# UI_MAIN.net
KiCad netlist of a schematic drawn in Altium Designer
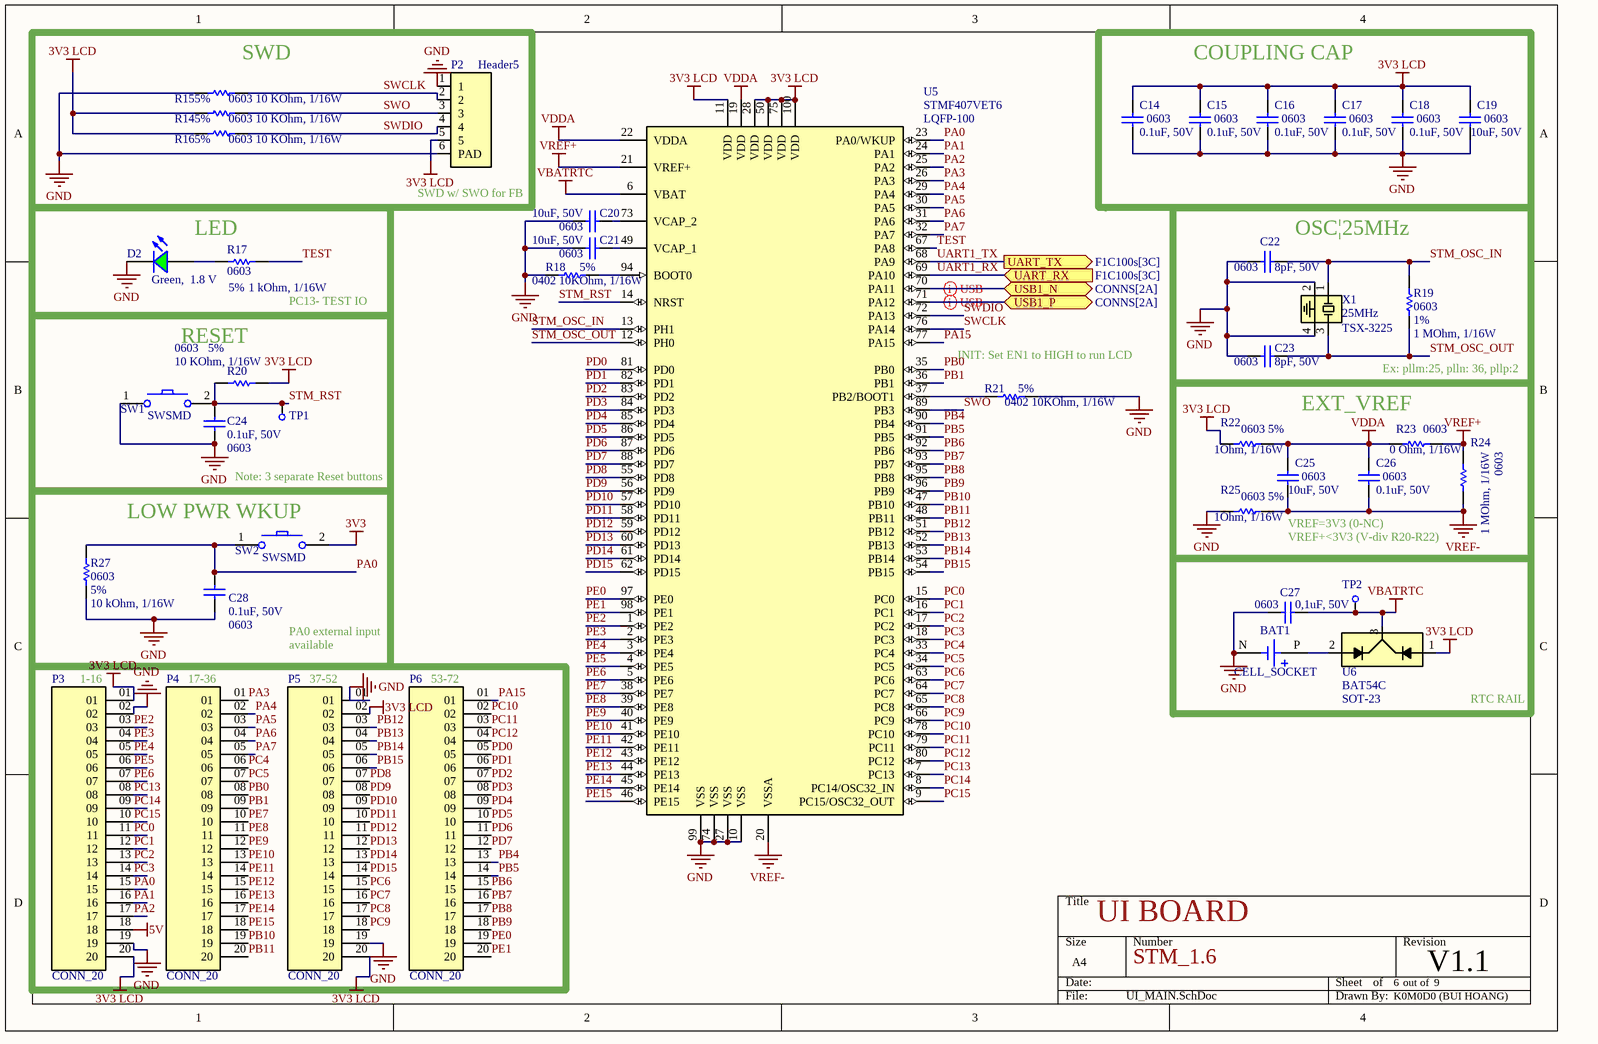
[diagram p0: UI_MAIN.SchDoc]

(export (version "E")
  (design (tool "Eeschema 10.0.6"))
  (components
    (comp (ref "BAT1")
      (value "CELL_SOCKET")
      (footprint "CELL_SOCKET")
      (description "Battery Holder (CELL_PIN)")
      (libsource (lib "DisplayLib") (part "CELL_SOCKET"))
    )
    (comp (ref "C14")
      (value "0.1uF, 50V")
      (footprint "C_0603")
      (description "CAP_0603")
      (fields (field (name "PACKAGE") "0603"))
      (libsource (lib "DisplayLib") (part "CAP_0603"))
    )
    (comp (ref "C15")
      (value "0.1uF, 50V")
      (footprint "C_0603")
      (description "CAP_0603")
      (fields (field (name "PACKAGE") "0603"))
      (libsource (lib "DisplayLib") (part "CAP_0603"))
    )
    (comp (ref "C16")
      (value "0.1uF, 50V")
      (footprint "C_0603")
      (description "CAP_0603")
      (fields (field (name "PACKAGE") "0603"))
      (libsource (lib "DisplayLib") (part "CAP_0603"))
    )
    (comp (ref "C17")
      (value "0.1uF, 50V")
      (footprint "C_0603")
      (description "CAP_0603")
      (fields (field (name "PACKAGE") "0603"))
      (libsource (lib "DisplayLib") (part "CAP_0603"))
    )
    (comp (ref "C18")
      (value "0.1uF, 50V")
      (footprint "C_0603")
      (description "CAP_0603")
      (fields (field (name "PACKAGE") "0603"))
      (libsource (lib "DisplayLib") (part "CAP_0603"))
    )
    (comp (ref "C19")
      (value "10uF, 50V")
      (footprint "C_0603")
      (description "CAP_0603")
      (fields (field (name "PACKAGE") "0603"))
      (libsource (lib "DisplayLib") (part "CAP_0603"))
    )
    (comp (ref "C20")
      (value "10uF, 50V")
      (footprint "C_0603")
      (description "CAP_0603")
      (fields (field (name "PACKAGE") "0603"))
      (libsource (lib "DisplayLib") (part "CAP_0603"))
    )
    (comp (ref "C21")
      (value "10uF, 50V")
      (footprint "C_0603")
      (description "CAP_0603")
      (fields (field (name "PACKAGE") "0603"))
      (libsource (lib "DisplayLib") (part "CAP_0603"))
    )
    (comp (ref "C22")
      (value "8pF, 50V")
      (footprint "C_0603")
      (description "CAP_0603")
      (fields (field (name "PACKAGE") "0603"))
      (libsource (lib "DisplayLib") (part "CAP_0603"))
    )
    (comp (ref "C23")
      (value "8pF, 50V")
      (footprint "C_0603")
      (description "CAP_0603")
      (fields (field (name "PACKAGE") "0603"))
      (libsource (lib "DisplayLib") (part "CAP_0603"))
    )
    (comp (ref "C24")
      (value "0.1uF, 50V")
      (footprint "C_0603")
      (description "CAP_0603")
      (fields (field (name "PACKAGE") "0603"))
      (libsource (lib "DisplayLib") (part "CAP_0603"))
    )
    (comp (ref "C25")
      (value "10uF, 50V")
      (footprint "C_0603")
      (description "CAP_0603")
      (fields (field (name "PACKAGE") "0603"))
      (libsource (lib "DisplayLib") (part "CAP_0603"))
    )
    (comp (ref "C26")
      (value "0.1uF, 50V")
      (footprint "C_0603")
      (description "CAP_0603")
      (fields (field (name "PACKAGE") "0603"))
      (libsource (lib "DisplayLib") (part "CAP_0603"))
    )
    (comp (ref "C27")
      (value "0,1uF, 50V")
      (footprint "C_0603")
      (description "CAP_0603")
      (fields (field (name "PACKAGE") "0603"))
      (libsource (lib "DisplayLib") (part "CAP_0603"))
    )
    (comp (ref "C28")
      (value "0.1uF, 50V")
      (footprint "C_0603")
      (description "CAP_0603")
      (fields (field (name "PACKAGE") "0603"))
      (libsource (lib "DisplayLib") (part "CAP_0603"))
    )
    (comp (ref "D2")
      (value "Green,  1.8 V")
      (footprint "LED_0603")
      (description "Green LED")
      (libsource (lib "DisplayLib") (part "GREEN"))
    )
    (comp (ref "P2")
      (value "Header5")
      (footprint "CONN_Header5")
      (description "Header 5 pins (2.54mm)")
      (libsource (lib "DisplayLib") (part "HEADER5"))
    )
    (comp (ref "P3")
      (value "CONN_20")
      (footprint "CONN_20")
      (description "Header 20 pins (2.54mm)")
      (libsource (lib "DisplayLib") (part "CONN_20"))
    )
    (comp (ref "P4")
      (value "CONN_20")
      (footprint "CONN_20")
      (description "Header 20 pins (2.54mm)")
      (libsource (lib "DisplayLib") (part "CONN_20"))
    )
    (comp (ref "P5")
      (value "CONN_20")
      (footprint "CONN_20")
      (description "Header 20 pins (2.54mm)")
      (libsource (lib "DisplayLib") (part "CONN_20"))
    )
    (comp (ref "P6")
      (value "CONN_20")
      (footprint "CONN_20")
      (description "Header 20 pins (2.54mm)")
      (libsource (lib "DisplayLib") (part "CONN_20"))
    )
    (comp (ref "R14")
      (value "10 KOhm, 1/16W")
      (footprint "R_0603")
      (description "RES_0603")
      (fields (field (name "PACKAGE") "0603") (field (name "ACC") "5%"))
      (libsource (lib "DisplayLib") (part "RES_0603"))
    )
    (comp (ref "R15")
      (value "10 KOhm, 1/16W")
      (footprint "R_0603")
      (description "RES_0603")
      (fields (field (name "PACKAGE") "0603") (field (name "ACC") "5%"))
      (libsource (lib "DisplayLib") (part "RES_0603"))
    )
    (comp (ref "R16")
      (value "10 KOhm, 1/16W")
      (footprint "R_0603")
      (description "RES_0603")
      (fields (field (name "PACKAGE") "0603") (field (name "ACC") "5%"))
      (libsource (lib "DisplayLib") (part "RES_0603"))
    )
    (comp (ref "R17")
      (value "1 kOhm, 1/16W")
      (footprint "R_0603")
      (description "RES_0603")
      (fields (field (name "PACKAGE") "0603") (field (name "ACC") "5%"))
      (libsource (lib "DisplayLib") (part "RES_0603"))
    )
    (comp (ref "R18")
      (value "10KOhm, 1/16W")
      (footprint "R_0402")
      (description "RES_0402")
      (fields (field (name "PACKAGE") "0402") (field (name "ACC") "5%"))
      (libsource (lib "DisplayLib") (part "RES_0402"))
    )
    (comp (ref "R19")
      (value "1 MOhm, 1/16W")
      (footprint "R_0603")
      (description "RES_0603")
      (fields (field (name "PACKAGE") "0603") (field (name "ACC") "1%"))
      (libsource (lib "DisplayLib") (part "RES_0603"))
    )
    (comp (ref "R20")
      (value "10 KOhm, 1/16W")
      (footprint "R_0603")
      (description "RES_0603")
      (fields (field (name "PACKAGE") "0603") (field (name "ACC") "5%"))
      (libsource (lib "DisplayLib") (part "RES_0603"))
    )
    (comp (ref "R21")
      (value "10KOhm, 1/16W")
      (footprint "R_0402")
      (description "RES_0402")
      (fields (field (name "PACKAGE") "0402") (field (name "ACC") "5%"))
      (libsource (lib "DisplayLib") (part "RES_0402"))
    )
    (comp (ref "R22")
      (value "1Ohm, 1/16W")
      (footprint "R_0603")
      (description "RES_0603")
      (fields (field (name "PACKAGE") "0603") (field (name "ACC") "5%"))
      (libsource (lib "DisplayLib") (part "RES_0603"))
    )
    (comp (ref "R23")
      (value "0 Ohm, 1/16W")
      (footprint "R_0603")
      (description "RES_0603")
      (fields (field (name "PACKAGE") "0603"))
      (libsource (lib "DisplayLib") (part "RES_0603"))
    )
    (comp (ref "R24")
      (value "1 MOhm, 1/16W")
      (footprint "R_0603")
      (description "RES_0603")
      (fields (field (name "PACKAGE") "0603"))
      (libsource (lib "DisplayLib") (part "RES_0603"))
    )
    (comp (ref "R25")
      (value "1Ohm, 1/16W")
      (footprint "R_0603")
      (description "RES_0603")
      (fields (field (name "PACKAGE") "0603") (field (name "ACC") "5%"))
      (libsource (lib "DisplayLib") (part "RES_0603"))
    )
    (comp (ref "R27")
      (value "10 kOhm, 1/16W")
      (footprint "R_0603")
      (description "RES_0603")
      (fields (field (name "PACKAGE") "0603") (field (name "ACC") "5%"))
      (libsource (lib "DisplayLib") (part "RES_0603"))
    )
    (comp (ref "SW1")
      (value "SWSMD")
      (footprint "SW_SMD_NOGND")
      (description "SW_SMD")
      (libsource (lib "DisplayLib") (part "SWSMD_NOGND"))
    )
    (comp (ref "SW2")
      (value "SWSMD")
      (footprint "SW_SMD_NOGND")
      (description "SW_SMD")
      (libsource (lib "DisplayLib") (part "SWSMD_NOGND"))
    )
    (comp (ref "TP1")
      (value "TESTPT")
      (footprint "TESTPT")
      (description "Test point")
      (libsource (lib "DisplayLib") (part "TESTPT"))
    )
    (comp (ref "TP2")
      (value "TESTPT")
      (footprint "TESTPT")
      (description "Test point")
      (libsource (lib "DisplayLib") (part "TESTPT"))
    )
    (comp (ref "U5")
      (value "STMF407VET6")
      (footprint "PKG_LQFP-100")
      (fields (field (name "PACKAGE") "LQFP-100"))
      (libsource (lib "DisplayLib") (part "STMF407VET6"))
    )
    (comp (ref "U6")
      (value "BAT54C")
      (footprint "PKG_SOT-23")
      (description "P-Channel 30 V 4A (Ta) 1.4W (Ta) Surface Mount SOT-23-3")
      (fields (field (name "PACKAGE") "SOT-23"))
      (libsource (lib "DisplayLib") (part "BAT54C"))
    )
    (comp (ref "X1")
      (value "25MHz")
      (footprint "PKG_TSX-3225")
      (description "Crystal, 25 MHz, -30 to 85 degC, 3.2 x 2.5 x 0.9 mm SMD")
      (fields (field (name "PACKAGE") "TSX-3225"))
      (libsource (lib "DisplayLib") (part "XTAL"))
    )
  )
  (nets
    (net (code "1") (name "/PA0") (class "Default")
      (node (ref "C28") (pin "2") (pinfunction "2_2") (pintype "passive"))
      (node (ref "P3") (pin "15") (pinfunction "15_15") (pintype "passive"))
      (node (ref "R27") (pin "2") (pinfunction "2_2") (pintype "passive"))
      (node (ref "SW2") (pin "1") (pinfunction "1_1") (pintype "passive"))
      (node (ref "U5") (pin "23") (pinfunction "PA0/WKUP_23") (pintype "bidirectional"))
    )
    (net (code "2") (name "/PA1") (class "Default")
      (node (ref "P3") (pin "16") (pinfunction "16_16") (pintype "passive"))
      (node (ref "U5") (pin "24") (pinfunction "PA1_24") (pintype "bidirectional"))
    )
    (net (code "3") (name "/PA2") (class "Default")
      (node (ref "P3") (pin "17") (pinfunction "17_17") (pintype "passive"))
      (node (ref "U5") (pin "25") (pinfunction "PA2_25") (pintype "bidirectional"))
    )
    (net (code "4") (name "/PA3") (class "Default")
      (node (ref "P4") (pin "01") (pinfunction "01_01") (pintype "passive"))
      (node (ref "U5") (pin "26") (pinfunction "PA3_26") (pintype "bidirectional"))
    )
    (net (code "5") (name "/PA4") (class "Default")
      (node (ref "P4") (pin "02") (pinfunction "02_02") (pintype "passive"))
      (node (ref "U5") (pin "29") (pinfunction "PA4_29") (pintype "bidirectional"))
    )
    (net (code "6") (name "/PA5") (class "Default")
      (node (ref "P4") (pin "03") (pinfunction "03_03") (pintype "passive"))
      (node (ref "U5") (pin "30") (pinfunction "PA5_30") (pintype "bidirectional"))
    )
    (net (code "7") (name "/PA6") (class "Default")
      (node (ref "P4") (pin "04") (pinfunction "04_04") (pintype "passive"))
      (node (ref "U5") (pin "31") (pinfunction "PA6_31") (pintype "bidirectional"))
    )
    (net (code "8") (name "/PA7") (class "Default")
      (node (ref "P4") (pin "05") (pinfunction "05_05") (pintype "passive"))
      (node (ref "U5") (pin "32") (pinfunction "PA7_32") (pintype "bidirectional"))
    )
    (net (code "9") (name "/PA15") (class "Default")
      (node (ref "P6") (pin "01") (pinfunction "01_01") (pintype "passive"))
      (node (ref "U5") (pin "77") (pinfunction "PA15_77") (pintype "bidirectional"))
    )
    (net (code "10") (name "/PB0") (class "Default")
      (node (ref "P4") (pin "08") (pinfunction "08_08") (pintype "passive"))
      (node (ref "U5") (pin "35") (pinfunction "PB0_35") (pintype "bidirectional"))
    )
    (net (code "11") (name "/PB1") (class "Default")
      (node (ref "P4") (pin "09") (pinfunction "09_09") (pintype "passive"))
      (node (ref "U5") (pin "36") (pinfunction "PB1_36") (pintype "bidirectional"))
    )
    (net (code "12") (name "/PB4") (class "Default")
      (node (ref "P6") (pin "13") (pinfunction "13_13") (pintype "passive"))
      (node (ref "U5") (pin "90") (pinfunction "PB4_90") (pintype "bidirectional"))
    )
    (net (code "13") (name "/PB5") (class "Default")
      (node (ref "P6") (pin "14") (pinfunction "14_14") (pintype "passive"))
      (node (ref "U5") (pin "91") (pinfunction "PB5_91") (pintype "bidirectional"))
    )
    (net (code "14") (name "/PB6") (class "Default")
      (node (ref "P6") (pin "15") (pinfunction "15_15") (pintype "passive"))
      (node (ref "U5") (pin "92") (pinfunction "PB6_92") (pintype "bidirectional"))
    )
    (net (code "15") (name "/PB7") (class "Default")
      (node (ref "P6") (pin "16") (pinfunction "16_16") (pintype "passive"))
      (node (ref "U5") (pin "93") (pinfunction "PB7_93") (pintype "bidirectional"))
    )
    (net (code "16") (name "/PB8") (class "Default")
      (node (ref "P6") (pin "17") (pinfunction "17_17") (pintype "passive"))
      (node (ref "U5") (pin "95") (pinfunction "PB8_95") (pintype "bidirectional"))
    )
    (net (code "17") (name "/PB9") (class "Default")
      (node (ref "P6") (pin "18") (pinfunction "18_18") (pintype "passive"))
      (node (ref "U5") (pin "96") (pinfunction "PB9_96") (pintype "bidirectional"))
    )
    (net (code "18") (name "/PB10") (class "Default")
      (node (ref "P4") (pin "19") (pinfunction "19_19") (pintype "passive"))
      (node (ref "U5") (pin "47") (pinfunction "PB10_47") (pintype "bidirectional"))
    )
    (net (code "19") (name "/PB11") (class "Default")
      (node (ref "P4") (pin "20") (pinfunction "20_20") (pintype "passive"))
      (node (ref "U5") (pin "48") (pinfunction "PB11_48") (pintype "bidirectional"))
    )
    (net (code "20") (name "/PB12") (class "Default")
      (node (ref "P5") (pin "03") (pinfunction "03_03") (pintype "passive"))
      (node (ref "U5") (pin "51") (pinfunction "PB12_51") (pintype "bidirectional"))
    )
    (net (code "21") (name "/PB13") (class "Default")
      (node (ref "P5") (pin "04") (pinfunction "04_04") (pintype "passive"))
      (node (ref "U5") (pin "52") (pinfunction "PB13_52") (pintype "bidirectional"))
    )
    (net (code "22") (name "/PB14") (class "Default")
      (node (ref "P5") (pin "05") (pinfunction "05_05") (pintype "passive"))
      (node (ref "U5") (pin "53") (pinfunction "PB14_53") (pintype "bidirectional"))
    )
    (net (code "23") (name "/PB15") (class "Default")
      (node (ref "P5") (pin "06") (pinfunction "06_06") (pintype "passive"))
      (node (ref "U5") (pin "54") (pinfunction "PB15_54") (pintype "bidirectional"))
    )
    (net (code "24") (name "/PC0") (class "Default")
      (node (ref "P3") (pin "11") (pinfunction "11_11") (pintype "passive"))
      (node (ref "U5") (pin "15") (pinfunction "PC0_15") (pintype "bidirectional"))
    )
    (net (code "25") (name "/PC1") (class "Default")
      (node (ref "P3") (pin "12") (pinfunction "12_12") (pintype "passive"))
      (node (ref "U5") (pin "16") (pinfunction "PC1_16") (pintype "bidirectional"))
    )
    (net (code "26") (name "/PC2") (class "Default")
      (node (ref "P3") (pin "13") (pinfunction "13_13") (pintype "passive"))
      (node (ref "U5") (pin "17") (pinfunction "PC2_17") (pintype "bidirectional"))
    )
    (net (code "27") (name "/PC3") (class "Default")
      (node (ref "P3") (pin "14") (pinfunction "14_14") (pintype "passive"))
      (node (ref "U5") (pin "18") (pinfunction "PC3_18") (pintype "bidirectional"))
    )
    (net (code "28") (name "/PC4") (class "Default")
      (node (ref "P4") (pin "06") (pinfunction "06_06") (pintype "passive"))
      (node (ref "U5") (pin "33") (pinfunction "PC4_33") (pintype "bidirectional"))
    )
    (net (code "29") (name "/PC5") (class "Default")
      (node (ref "P4") (pin "07") (pinfunction "07_07") (pintype "passive"))
      (node (ref "U5") (pin "34") (pinfunction "PC5_34") (pintype "bidirectional"))
    )
    (net (code "30") (name "/PC6") (class "Default")
      (node (ref "P5") (pin "15") (pinfunction "15_15") (pintype "passive"))
      (node (ref "U5") (pin "63") (pinfunction "PC6_63") (pintype "bidirectional"))
    )
    (net (code "31") (name "/PC7") (class "Default")
      (node (ref "P5") (pin "16") (pinfunction "16_16") (pintype "passive"))
      (node (ref "U5") (pin "64") (pinfunction "PC7_64") (pintype "bidirectional"))
    )
    (net (code "32") (name "/PC8") (class "Default")
      (node (ref "P5") (pin "17") (pinfunction "17_17") (pintype "passive"))
      (node (ref "U5") (pin "65") (pinfunction "PC8_65") (pintype "bidirectional"))
    )
    (net (code "33") (name "/PC9") (class "Default")
      (node (ref "P5") (pin "18") (pinfunction "18_18") (pintype "passive"))
      (node (ref "U5") (pin "66") (pinfunction "PC9_66") (pintype "bidirectional"))
    )
    (net (code "34") (name "/PC10") (class "Default")
      (node (ref "P6") (pin "02") (pinfunction "02_02") (pintype "passive"))
      (node (ref "U5") (pin "78") (pinfunction "PC10_78") (pintype "bidirectional"))
    )
    (net (code "35") (name "/PC11") (class "Default")
      (node (ref "P6") (pin "03") (pinfunction "03_03") (pintype "passive"))
      (node (ref "U5") (pin "79") (pinfunction "PC11_79") (pintype "bidirectional"))
    )
    (net (code "36") (name "/PC12") (class "Default")
      (node (ref "P6") (pin "04") (pinfunction "04_04") (pintype "passive"))
      (node (ref "U5") (pin "80") (pinfunction "PC12_80") (pintype "bidirectional"))
    )
    (net (code "37") (name "/PC13") (class "Default")
      (node (ref "P3") (pin "08") (pinfunction "08_08") (pintype "passive"))
      (node (ref "U5") (pin "7") (pinfunction "PC13_7") (pintype "bidirectional"))
    )
    (net (code "38") (name "/PC14") (class "Default")
      (node (ref "P3") (pin "09") (pinfunction "09_09") (pintype "passive"))
      (node (ref "U5") (pin "8") (pinfunction "PC14/OSC32_IN_8") (pintype "bidirectional"))
    )
    (net (code "39") (name "/PC15") (class "Default")
      (node (ref "P3") (pin "10") (pinfunction "10_10") (pintype "passive"))
      (node (ref "U5") (pin "9") (pinfunction "PC15/OSC32_OUT_9") (pintype "bidirectional"))
    )
    (net (code "40") (name "/PD0") (class "Default")
      (node (ref "P6") (pin "05") (pinfunction "05_05") (pintype "passive"))
      (node (ref "U5") (pin "81") (pinfunction "PD0_81") (pintype "bidirectional"))
    )
    (net (code "41") (name "/PD1") (class "Default")
      (node (ref "P6") (pin "06") (pinfunction "06_06") (pintype "passive"))
      (node (ref "U5") (pin "82") (pinfunction "PD1_82") (pintype "bidirectional"))
    )
    (net (code "42") (name "/PD2") (class "Default")
      (node (ref "P6") (pin "07") (pinfunction "07_07") (pintype "passive"))
      (node (ref "U5") (pin "83") (pinfunction "PD2_83") (pintype "bidirectional"))
    )
    (net (code "43") (name "/PD3") (class "Default")
      (node (ref "P6") (pin "08") (pinfunction "08_08") (pintype "passive"))
      (node (ref "U5") (pin "84") (pinfunction "PD3_84") (pintype "bidirectional"))
    )
    (net (code "44") (name "/PD4") (class "Default")
      (node (ref "P6") (pin "09") (pinfunction "09_09") (pintype "passive"))
      (node (ref "U5") (pin "85") (pinfunction "PD4_85") (pintype "bidirectional"))
    )
    (net (code "45") (name "/PD5") (class "Default")
      (node (ref "P6") (pin "10") (pinfunction "10_10") (pintype "passive"))
      (node (ref "U5") (pin "86") (pinfunction "PD5_86") (pintype "bidirectional"))
    )
    (net (code "46") (name "/PD6") (class "Default")
      (node (ref "P6") (pin "11") (pinfunction "11_11") (pintype "passive"))
      (node (ref "U5") (pin "87") (pinfunction "PD6_87") (pintype "bidirectional"))
    )
    (net (code "47") (name "/PD7") (class "Default")
      (node (ref "P6") (pin "12") (pinfunction "12_12") (pintype "passive"))
      (node (ref "U5") (pin "88") (pinfunction "PD7_88") (pintype "bidirectional"))
    )
    (net (code "48") (name "/PD8") (class "Default")
      (node (ref "P5") (pin "07") (pinfunction "07_07") (pintype "passive"))
      (node (ref "U5") (pin "55") (pinfunction "PD8_55") (pintype "bidirectional"))
    )
    (net (code "49") (name "/PD9") (class "Default")
      (node (ref "P5") (pin "08") (pinfunction "08_08") (pintype "passive"))
      (node (ref "U5") (pin "56") (pinfunction "PD9_56") (pintype "bidirectional"))
    )
    (net (code "50") (name "/PD10") (class "Default")
      (node (ref "P5") (pin "09") (pinfunction "09_09") (pintype "passive"))
      (node (ref "U5") (pin "57") (pinfunction "PD10_57") (pintype "bidirectional"))
    )
    (net (code "51") (name "/PD11") (class "Default")
      (node (ref "P5") (pin "10") (pinfunction "10_10") (pintype "passive"))
      (node (ref "U5") (pin "58") (pinfunction "PD11_58") (pintype "bidirectional"))
    )
    (net (code "52") (name "/PD12") (class "Default")
      (node (ref "P5") (pin "11") (pinfunction "11_11") (pintype "passive"))
      (node (ref "U5") (pin "59") (pinfunction "PD12_59") (pintype "bidirectional"))
    )
    (net (code "53") (name "/PD13") (class "Default")
      (node (ref "P5") (pin "12") (pinfunction "12_12") (pintype "passive"))
      (node (ref "U5") (pin "60") (pinfunction "PD13_60") (pintype "bidirectional"))
    )
    (net (code "54") (name "/PD14") (class "Default")
      (node (ref "P5") (pin "13") (pinfunction "13_13") (pintype "passive"))
      (node (ref "U5") (pin "61") (pinfunction "PD14_61") (pintype "bidirectional"))
    )
    (net (code "55") (name "/PD15") (class "Default")
      (node (ref "P5") (pin "14") (pinfunction "14_14") (pintype "passive"))
      (node (ref "U5") (pin "62") (pinfunction "PD15_62") (pintype "bidirectional"))
    )
    (net (code "56") (name "/PE0") (class "Default")
      (node (ref "P6") (pin "19") (pinfunction "19_19") (pintype "passive"))
      (node (ref "U5") (pin "97") (pinfunction "PE0_97") (pintype "bidirectional"))
    )
    (net (code "57") (name "/PE1") (class "Default")
      (node (ref "P6") (pin "20") (pinfunction "20_20") (pintype "passive"))
      (node (ref "U5") (pin "98") (pinfunction "PE1_98") (pintype "bidirectional"))
    )
    (net (code "58") (name "/PE2") (class "Default")
      (node (ref "P3") (pin "03") (pinfunction "03_03") (pintype "passive"))
      (node (ref "U5") (pin "1") (pinfunction "PE2_1") (pintype "bidirectional"))
    )
    (net (code "59") (name "/PE3") (class "Default")
      (node (ref "P3") (pin "04") (pinfunction "04_04") (pintype "passive"))
      (node (ref "U5") (pin "2") (pinfunction "PE3_2") (pintype "bidirectional"))
    )
    (net (code "60") (name "/PE4") (class "Default")
      (node (ref "P3") (pin "05") (pinfunction "05_05") (pintype "passive"))
      (node (ref "U5") (pin "3") (pinfunction "PE4_3") (pintype "bidirectional"))
    )
    (net (code "61") (name "/PE5") (class "Default")
      (node (ref "P3") (pin "06") (pinfunction "06_06") (pintype "passive"))
      (node (ref "U5") (pin "4") (pinfunction "PE5_4") (pintype "bidirectional"))
    )
    (net (code "62") (name "/PE6") (class "Default")
      (node (ref "P3") (pin "07") (pinfunction "07_07") (pintype "passive"))
      (node (ref "U5") (pin "5") (pinfunction "PE6_5") (pintype "bidirectional"))
    )
    (net (code "63") (name "/PE7") (class "Default")
      (node (ref "P4") (pin "10") (pinfunction "10_10") (pintype "passive"))
      (node (ref "U5") (pin "38") (pinfunction "PE7_38") (pintype "bidirectional"))
    )
    (net (code "64") (name "/PE8") (class "Default")
      (node (ref "P4") (pin "11") (pinfunction "11_11") (pintype "passive"))
      (node (ref "U5") (pin "39") (pinfunction "PE8_39") (pintype "bidirectional"))
    )
    (net (code "65") (name "/PE9") (class "Default")
      (node (ref "P4") (pin "12") (pinfunction "12_12") (pintype "passive"))
      (node (ref "U5") (pin "40") (pinfunction "PE9_40") (pintype "bidirectional"))
    )
    (net (code "66") (name "/PE10") (class "Default")
      (node (ref "P4") (pin "13") (pinfunction "13_13") (pintype "passive"))
      (node (ref "U5") (pin "41") (pinfunction "PE10_41") (pintype "bidirectional"))
    )
    (net (code "67") (name "/PE11") (class "Default")
      (node (ref "P4") (pin "14") (pinfunction "14_14") (pintype "passive"))
      (node (ref "U5") (pin "42") (pinfunction "PE11_42") (pintype "bidirectional"))
    )
    (net (code "68") (name "/PE12") (class "Default")
      (node (ref "P4") (pin "15") (pinfunction "15_15") (pintype "passive"))
      (node (ref "U5") (pin "43") (pinfunction "PE12_43") (pintype "bidirectional"))
    )
    (net (code "69") (name "/PE13") (class "Default")
      (node (ref "P4") (pin "16") (pinfunction "16_16") (pintype "passive"))
      (node (ref "U5") (pin "44") (pinfunction "PE13_44") (pintype "bidirectional"))
    )
    (net (code "70") (name "/PE14") (class "Default")
      (node (ref "P4") (pin "17") (pinfunction "17_17") (pintype "passive"))
      (node (ref "U5") (pin "45") (pinfunction "PE14_45") (pintype "bidirectional"))
    )
    (net (code "71") (name "/PE15") (class "Default")
      (node (ref "P4") (pin "18") (pinfunction "18_18") (pintype "passive"))
      (node (ref "U5") (pin "46") (pinfunction "PE15_46") (pintype "bidirectional"))
    )
    (net (code "72") (name "/STM_OSC_IN") (class "Default")
      (node (ref "C22") (pin "2") (pinfunction "2_2") (pintype "passive"))
      (node (ref "R19") (pin "2") (pinfunction "2_2") (pintype "passive"))
      (node (ref "U5") (pin "13") (pinfunction "PH1_13") (pintype "bidirectional"))
      (node (ref "X1") (pin "1") (pinfunction "1_1") (pintype "passive"))
    )
    (net (code "73") (name "/STM_OSC_OUT") (class "Default")
      (node (ref "C23") (pin "2") (pinfunction "2_2") (pintype "passive"))
      (node (ref "R19") (pin "1") (pinfunction "1_1") (pintype "passive"))
      (node (ref "U5") (pin "12") (pinfunction "PH0_12") (pintype "bidirectional"))
      (node (ref "X1") (pin "3") (pinfunction "3_3") (pintype "passive"))
    )
    (net (code "74") (name "/STM_RST") (class "Default")
      (node (ref "C24") (pin "2") (pinfunction "2_2") (pintype "passive"))
      (node (ref "R20") (pin "1") (pinfunction "1_1") (pintype "passive"))
      (node (ref "SW1") (pin "2") (pinfunction "2_2") (pintype "passive"))
      (node (ref "TP1") (pin "1") (pinfunction "1_1") (pintype "passive"))
      (node (ref "U5") (pin "14") (pinfunction "NRST_14") (pintype "bidirectional"))
    )
    (net (code "75") (name "/SWCLK") (class "Default")
      (node (ref "P2") (pin "2") (pinfunction "2_2") (pintype "passive"))
      (node (ref "R15") (pin "2") (pinfunction "2_2") (pintype "passive"))
      (node (ref "U5") (pin "76") (pinfunction "PA14_76") (pintype "bidirectional"))
    )
    (net (code "76") (name "/SWDIO") (class "Default")
      (node (ref "P2") (pin "4") (pinfunction "4_4") (pintype "passive"))
      (node (ref "R16") (pin "2") (pinfunction "2_2") (pintype "passive"))
      (node (ref "U5") (pin "72") (pinfunction "PA13_72") (pintype "bidirectional"))
    )
    (net (code "77") (name "/SWO") (class "Default")
      (node (ref "P2") (pin "3") (pinfunction "3_3") (pintype "passive"))
      (node (ref "R14") (pin "2") (pinfunction "2_2") (pintype "passive"))
      (node (ref "U5") (pin "89") (pinfunction "PB3_89") (pintype "bidirectional"))
    )
    (net (code "78") (name "/TEST") (class "Default")
      (node (ref "R17") (pin "2") (pinfunction "2_2") (pintype "passive"))
      (node (ref "U5") (pin "67") (pinfunction "PA8_67") (pintype "bidirectional"))
    )
    (net (code "79") (name "/UART1_RX") (class "Default")
      (node (ref "U5") (pin "69") (pinfunction "PA10_69") (pintype "bidirectional"))
    )
    (net (code "80") (name "/UART1_TX") (class "Default")
      (node (ref "U5") (pin "68") (pinfunction "PA9_68") (pintype "bidirectional"))
    )
    (net (code "81") (name "/USB1_N") (class "Default")
      (node (ref "U5") (pin "70") (pinfunction "PA11_70") (pintype "bidirectional"))
    )
    (net (code "82") (name "/USB1_P") (class "Default")
      (node (ref "U5") (pin "71") (pinfunction "PA12_71") (pintype "bidirectional"))
    )
    (net (code "83") (name "3V3") (class "Default")
      (node (ref "SW2") (pin "2") (pinfunction "2_2") (pintype "passive"))
    )
    (net (code "84") (name "3V3 LCD") (class "Default")
      (node (ref "C14") (pin "2") (pinfunction "2_2") (pintype "passive"))
      (node (ref "C15") (pin "2") (pinfunction "2_2") (pintype "passive"))
      (node (ref "C16") (pin "2") (pinfunction "2_2") (pintype "passive"))
      (node (ref "C17") (pin "2") (pinfunction "2_2") (pintype "passive"))
      (node (ref "C18") (pin "2") (pinfunction "2_2") (pintype "passive"))
      (node (ref "C19") (pin "2") (pinfunction "2_2") (pintype "passive"))
      (node (ref "P2") (pin "5") (pinfunction "5_5") (pintype "passive"))
      (node (ref "P3") (pin "01") (pinfunction "01_01") (pintype "passive"))
      (node (ref "P3") (pin "20") (pinfunction "20_20") (pintype "passive"))
      (node (ref "P5") (pin "02") (pinfunction "02_02") (pintype "passive"))
      (node (ref "P5") (pin "20") (pinfunction "20_20") (pintype "passive"))
      (node (ref "R14") (pin "1") (pinfunction "1_1") (pintype "passive"))
      (node (ref "R16") (pin "1") (pinfunction "1_1") (pintype "passive"))
      (node (ref "R20") (pin "2") (pinfunction "2_2") (pintype "passive"))
      (node (ref "R22") (pin "1") (pinfunction "1_1") (pintype "passive"))
      (node (ref "U5") (pin "100") (pinfunction "VDD_100") (pintype "power_in"))
      (node (ref "U5") (pin "11") (pinfunction "VDD_11") (pintype "power_in"))
      (node (ref "U5") (pin "28") (pinfunction "VDD_28") (pintype "power_in"))
      (node (ref "U5") (pin "50") (pinfunction "VDD_50") (pintype "power_in"))
      (node (ref "U5") (pin "75") (pinfunction "VDD_75") (pintype "power_in"))
      (node (ref "U6") (pin "1") (pinfunction "1_1") (pintype "power_in"))
    )
    (net (code "85") (name "5V") (class "Default")
      (node (ref "P3") (pin "18") (pinfunction "18_18") (pintype "passive"))
    )
    (net (code "86") (name "GND") (class "Default")
      (node (ref "BAT1") (pin "N") (pinfunction "N_N") (pintype "passive"))
      (node (ref "C14") (pin "1") (pinfunction "1_1") (pintype "passive"))
      (node (ref "C15") (pin "1") (pinfunction "1_1") (pintype "passive"))
      (node (ref "C16") (pin "1") (pinfunction "1_1") (pintype "passive"))
      (node (ref "C17") (pin "1") (pinfunction "1_1") (pintype "passive"))
      (node (ref "C18") (pin "1") (pinfunction "1_1") (pintype "passive"))
      (node (ref "C19") (pin "1") (pinfunction "1_1") (pintype "passive"))
      (node (ref "C20") (pin "2") (pinfunction "2_2") (pintype "passive"))
      (node (ref "C21") (pin "2") (pinfunction "2_2") (pintype "passive"))
      (node (ref "C22") (pin "1") (pinfunction "1_1") (pintype "passive"))
      (node (ref "C23") (pin "1") (pinfunction "1_1") (pintype "passive"))
      (node (ref "C24") (pin "1") (pinfunction "1_1") (pintype "passive"))
      (node (ref "C27") (pin "1") (pinfunction "1_1") (pintype "passive"))
      (node (ref "C28") (pin "1") (pinfunction "1_1") (pintype "passive"))
      (node (ref "D2") (pin "1") (pinfunction "K_1") (pintype "passive"))
      (node (ref "P2") (pin "1") (pinfunction "1_1") (pintype "passive"))
      (node (ref "P2") (pin "6") (pinfunction "PAD_6") (pintype "passive"))
      (node (ref "P3") (pin "02") (pinfunction "02_02") (pintype "passive"))
      (node (ref "P3") (pin "19") (pinfunction "19_19") (pintype "passive"))
      (node (ref "P5") (pin "01") (pinfunction "01_01") (pintype "passive"))
      (node (ref "P5") (pin "19") (pinfunction "19_19") (pintype "passive"))
      (node (ref "R15") (pin "1") (pinfunction "1_1") (pintype "passive"))
      (node (ref "R18") (pin "1") (pinfunction "1_1") (pintype "passive"))
      (node (ref "R21") (pin "2") (pinfunction "2_2") (pintype "passive"))
      (node (ref "R25") (pin "1") (pinfunction "1_1") (pintype "passive"))
      (node (ref "R27") (pin "1") (pinfunction "1_1") (pintype "passive"))
      (node (ref "SW1") (pin "1") (pinfunction "1_1") (pintype "passive"))
      (node (ref "U5") (pin "10") (pinfunction "VSS_10") (pintype "power_in"))
      (node (ref "U5") (pin "27") (pinfunction "VSS_27") (pintype "power_in"))
      (node (ref "U5") (pin "74") (pinfunction "VSS_74") (pintype "power_in"))
      (node (ref "U5") (pin "99") (pinfunction "VSS_99") (pintype "power_in"))
      (node (ref "X1") (pin "2") (pinfunction "2_2") (pintype "passive"))
      (node (ref "X1") (pin "4") (pinfunction "4_4") (pintype "passive"))
    )
    (net (code "87") (name "Net-(BAT1-PadP)") (class "Default")
      (node (ref "BAT1") (pin "P") (pinfunction "P_P") (pintype "passive"))
      (node (ref "U6") (pin "2") (pinfunction "2_2") (pintype "passive"))
    )
    (net (code "88") (name "Net-(D2-A)") (class "Default")
      (node (ref "D2") (pin "2") (pinfunction "A_2") (pintype "passive"))
      (node (ref "R17") (pin "1") (pinfunction "1_1") (pintype "passive"))
    )
    (net (code "89") (name "Net-(U5-BOOT0)") (class "Default")
      (node (ref "R18") (pin "2") (pinfunction "2_2") (pintype "passive"))
      (node (ref "U5") (pin "94") (pinfunction "BOOT0_94") (pintype "input"))
    )
    (net (code "90") (name "Net-(U5-PB2{slash}BOOT1)") (class "Default")
      (node (ref "R21") (pin "1") (pinfunction "1_1") (pintype "passive"))
      (node (ref "U5") (pin "37") (pinfunction "PB2/BOOT1_37") (pintype "bidirectional"))
    )
    (net (code "91") (name "Net-(U5-VCAP_1)") (class "Default")
      (node (ref "C21") (pin "1") (pinfunction "1_1") (pintype "passive"))
      (node (ref "U5") (pin "49") (pinfunction "VCAP_1_49") (pintype "power_in"))
    )
    (net (code "92") (name "Net-(U5-VCAP_2)") (class "Default")
      (node (ref "C20") (pin "1") (pinfunction "1_1") (pintype "passive"))
      (node (ref "U5") (pin "73") (pinfunction "VCAP_2_73") (pintype "power_in"))
    )
    (net (code "93") (name "VBATRTC") (class "Default")
      (node (ref "C27") (pin "2") (pinfunction "2_2") (pintype "passive"))
      (node (ref "TP2") (pin "1") (pinfunction "1_1") (pintype "passive"))
      (node (ref "U5") (pin "6") (pinfunction "VBAT_6") (pintype "power_in"))
      (node (ref "U6") (pin "3") (pinfunction "3_3") (pintype "passive"))
    )
    (net (code "94") (name "VDDA") (class "Default")
      (node (ref "C25") (pin "2") (pinfunction "2_2") (pintype "passive"))
      (node (ref "C26") (pin "2") (pinfunction "2_2") (pintype "passive"))
      (node (ref "R22") (pin "2") (pinfunction "2_2") (pintype "passive"))
      (node (ref "R23") (pin "1") (pinfunction "1_1") (pintype "passive"))
      (node (ref "U5") (pin "19") (pinfunction "VDD_19") (pintype "power_in"))
      (node (ref "U5") (pin "22") (pinfunction "VDDA_22") (pintype "power_in"))
    )
    (net (code "95") (name "VREF+") (class "Default")
      (node (ref "R23") (pin "2") (pinfunction "2_2") (pintype "passive"))
      (node (ref "R24") (pin "2") (pinfunction "2_2") (pintype "passive"))
      (node (ref "U5") (pin "21") (pinfunction "VREF+_21") (pintype "power_in"))
    )
    (net (code "96") (name "VREF-") (class "Default")
      (node (ref "C25") (pin "1") (pinfunction "1_1") (pintype "passive"))
      (node (ref "C26") (pin "1") (pinfunction "1_1") (pintype "passive"))
      (node (ref "R24") (pin "1") (pinfunction "1_1") (pintype "passive"))
      (node (ref "R25") (pin "2") (pinfunction "2_2") (pintype "passive"))
      (node (ref "U5") (pin "20") (pinfunction "VSSA_20") (pintype "power_in"))
    )
  )
)
